# BonkSwitch.net
KiCad netlist of a schematic drawn in EAGLE
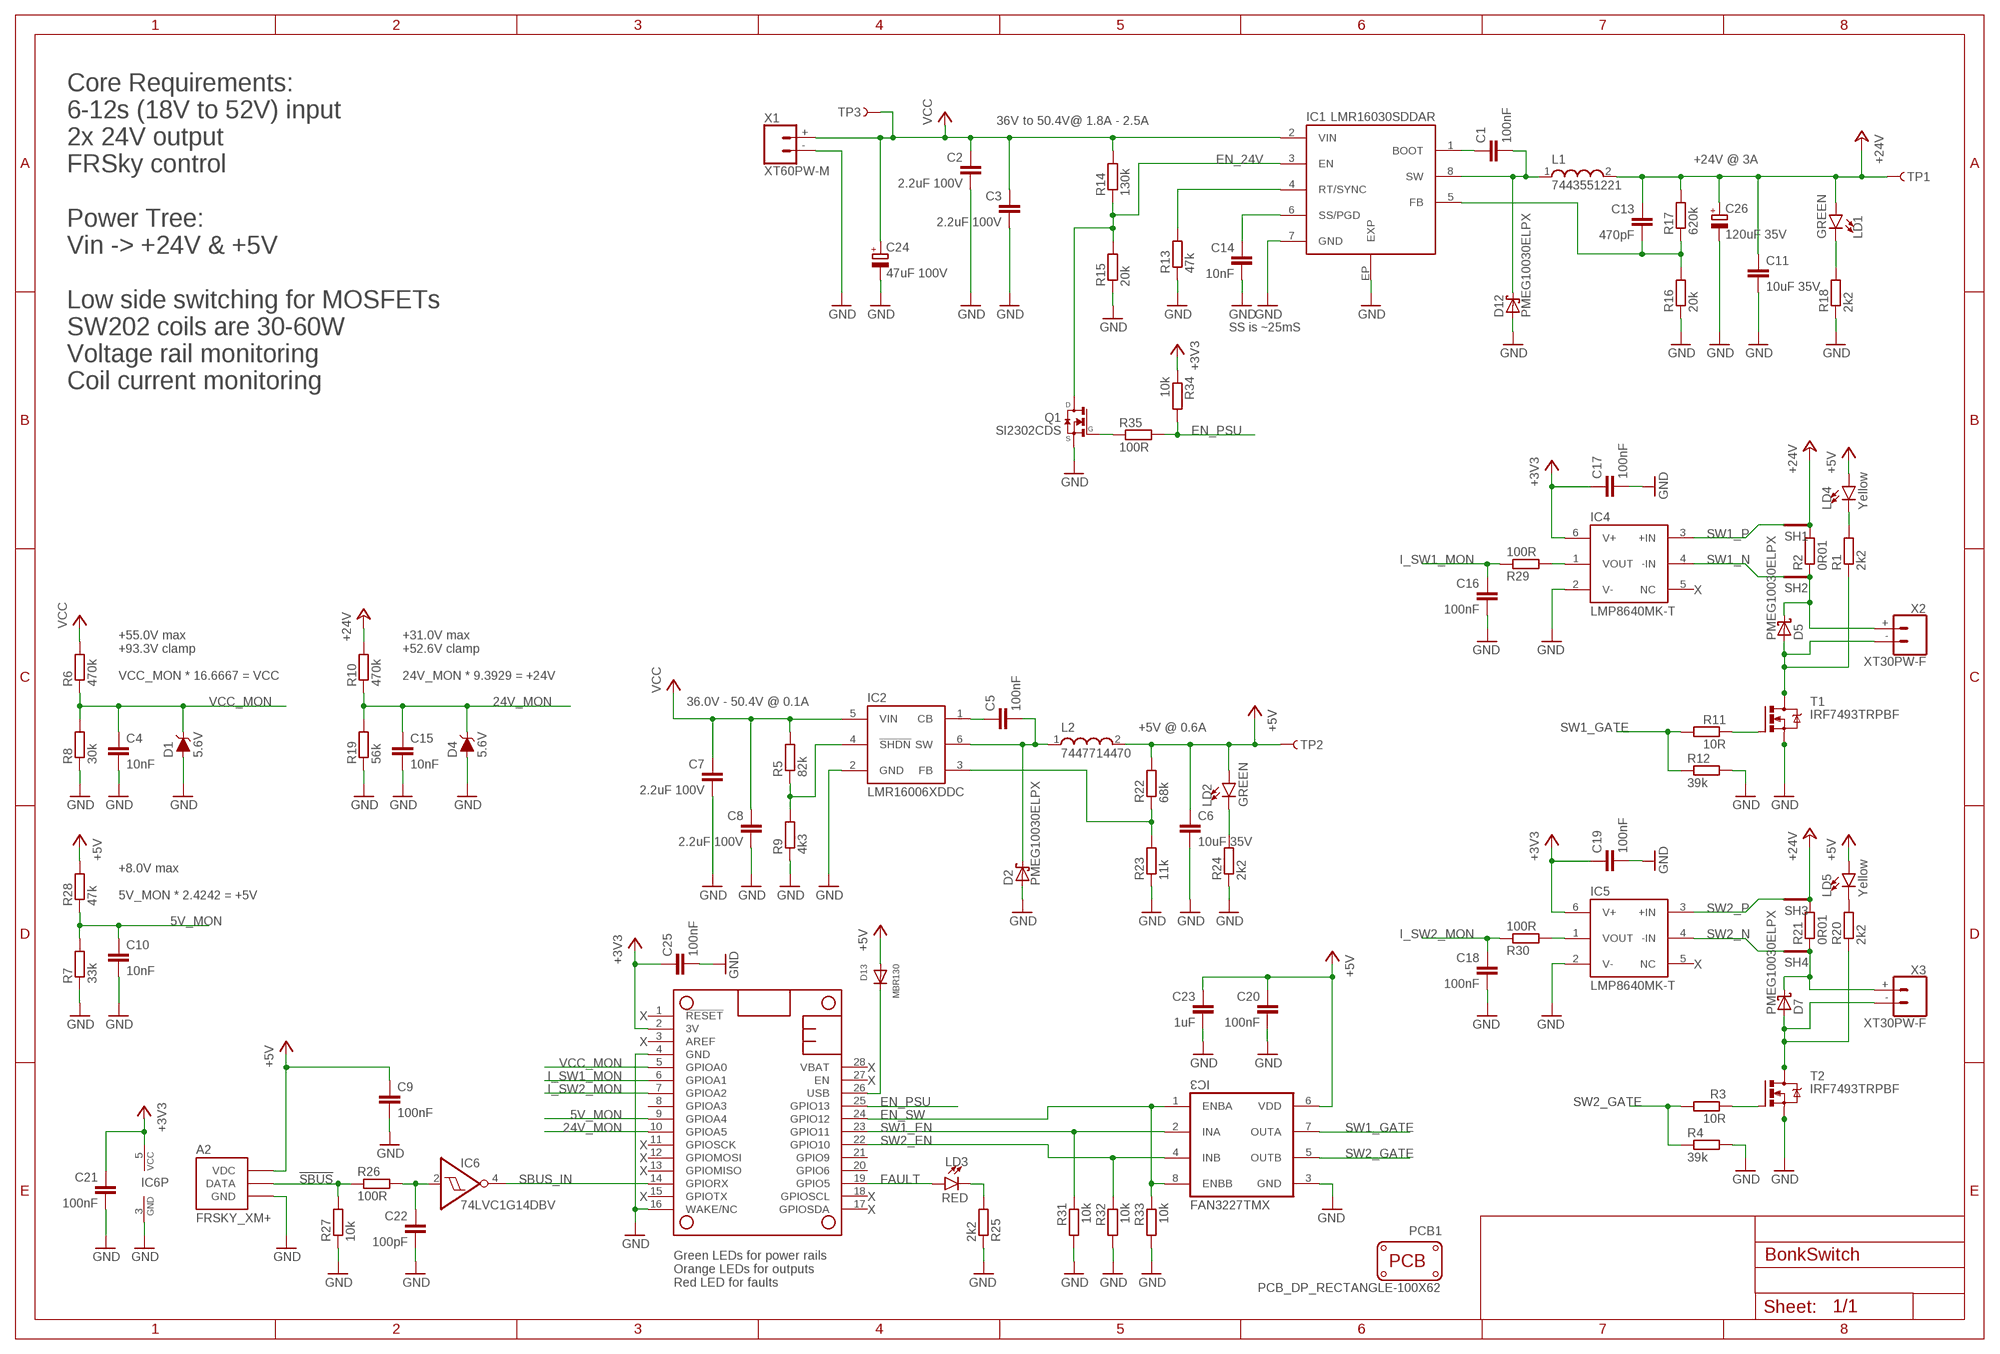
[diagram p0: schematic, sheet 1]

(export (version "E")
  (design (tool "Eeschema 10.0.6"))
  (components
    (comp (ref "A1")
      (value "FEATHERWING_NODIM")
      (footprint "eagle-import:FEATHERWING_DIM")
      (libsource (lib "eagle-import") (part "FEATHERWING_NODIM"))
    )
    (comp (ref "A2")
      (value "FRSKY_XM+")
      (footprint "eagle-import:FRSKY_XM+")
      (libsource (lib "eagle-import") (part "FRSKY_XM+"))
    )
    (comp (ref "C1")
      (value "100nF")
      (footprint "eagle-import:C0603")
      (libsource (lib "eagle-import") (part "C-EUC0603"))
    )
    (comp (ref "C2")
      (value "2.2uF 100V")
      (footprint "eagle-import:C1210")
      (fields (field (name "MF") "TDK") (field (name "MPN") "C3225X7R2A225K230AB"))
      (libsource (lib "eagle-import") (part "C-EUC1210"))
    )
    (comp (ref "C3")
      (value "2.2uF 100V")
      (footprint "eagle-import:C1210")
      (fields (field (name "MF") "TDK") (field (name "MPN") "C3225X7R2A225K230AB"))
      (libsource (lib "eagle-import") (part "C-EUC1210"))
    )
    (comp (ref "C4")
      (value "10nF")
      (footprint "eagle-import:C0603")
      (libsource (lib "eagle-import") (part "C-EUC0603"))
    )
    (comp (ref "C5")
      (value "100nF")
      (footprint "eagle-import:C0603")
      (libsource (lib "eagle-import") (part "C-EUC0603"))
    )
    (comp (ref "C6")
      (value "10uF 35V")
      (footprint "eagle-import:C1210")
      (fields (field (name "MF") "TAIYO YUDEN") (field (name "MPN") "GMK325AB7106MM-T"))
      (libsource (lib "eagle-import") (part "C-EUC1210"))
    )
    (comp (ref "C7")
      (value "2.2uF 100V")
      (footprint "eagle-import:C1210")
      (fields (field (name "MF") "TDK") (field (name "MPN") "C3225X7R2A225K230AB"))
      (libsource (lib "eagle-import") (part "C-EUC1210"))
    )
    (comp (ref "C8")
      (value "2.2uF 100V")
      (footprint "eagle-import:C1210")
      (fields (field (name "MF") "TDK") (field (name "MPN") "C3225X7R2A225K230AB"))
      (libsource (lib "eagle-import") (part "C-EUC1210"))
    )
    (comp (ref "C9")
      (value "100nF")
      (footprint "eagle-import:C0603")
      (libsource (lib "eagle-import") (part "C-EUC0603"))
    )
    (comp (ref "C10")
      (value "10nF")
      (footprint "eagle-import:C0603")
      (libsource (lib "eagle-import") (part "C-EUC0603"))
    )
    (comp (ref "C11")
      (value "10uF 35V")
      (footprint "eagle-import:C1210")
      (fields (field (name "MF") "TAIYO YUDEN") (field (name "MPN") "GMK325AB7106MM-T"))
      (libsource (lib "eagle-import") (part "C-EUC1210"))
    )
    (comp (ref "C13")
      (value "470pF")
      (footprint "eagle-import:C0603")
      (libsource (lib "eagle-import") (part "C-EUC0603"))
    )
    (comp (ref "C14")
      (value "10nF")
      (footprint "eagle-import:C0603")
      (libsource (lib "eagle-import") (part "C-EUC0603"))
    )
    (comp (ref "C15")
      (value "10nF")
      (footprint "eagle-import:C0603")
      (libsource (lib "eagle-import") (part "C-EUC0603"))
    )
    (comp (ref "C16")
      (value "100nF")
      (footprint "eagle-import:C0603")
      (libsource (lib "eagle-import") (part "C-EUC0603"))
    )
    (comp (ref "C17")
      (value "100nF")
      (footprint "eagle-import:C0603")
      (libsource (lib "eagle-import") (part "C-EUC0603"))
    )
    (comp (ref "C18")
      (value "100nF")
      (footprint "eagle-import:C0603")
      (libsource (lib "eagle-import") (part "C-EUC0603"))
    )
    (comp (ref "C19")
      (value "100nF")
      (footprint "eagle-import:C0603")
      (libsource (lib "eagle-import") (part "C-EUC0603"))
    )
    (comp (ref "C20")
      (value "100nF")
      (footprint "eagle-import:C0603")
      (libsource (lib "eagle-import") (part "C-EUC0603"))
    )
    (comp (ref "C21")
      (value "100nF")
      (footprint "eagle-import:C0603")
      (libsource (lib "eagle-import") (part "C-EUC0603"))
    )
    (comp (ref "C22")
      (value "100pF")
      (footprint "eagle-import:C0603")
      (libsource (lib "eagle-import") (part "C-EUC0603"))
    )
    (comp (ref "C23")
      (value "1uF")
      (footprint "eagle-import:C0805")
      (libsource (lib "eagle-import") (part "C-EUC0805"))
    )
    (comp (ref "C24")
      (value "47uF 100V")
      (footprint "eagle-import:UD-10X10_NICHICON")
      (fields (field (name "MF") "PANASONIC") (field (name "MPN") "EEEHA2A470UP"))
      (libsource (lib "eagle-import") (part "CPOL-EUUD-10X10"))
    )
    (comp (ref "C25")
      (value "100nF")
      (footprint "eagle-import:C0603")
      (libsource (lib "eagle-import") (part "C-EUC0603"))
    )
    (comp (ref "C26")
      (value "120uF 35V")
      (footprint "eagle-import:PANASONIC_E")
      (fields (field (name "MF") "PANASONIC") (field (name "MPN") "35SVPF120M"))
      (libsource (lib "eagle-import") (part "CPOL-EUE"))
    )
    (comp (ref "D1")
      (value "5.6V")
      (footprint "eagle-import:SOD-323")
      (fields (field (name "MF") "ON SEMICONDUCTOR") (field (name "MPN") "MM3Z4V3ST1G"))
      (libsource (lib "eagle-import") (part "DIODE-ZENER-MMSZ5232BS"))
    )
    (comp (ref "D2")
      (value "PMEG10030ELPX")
      (footprint "eagle-import:SOD128")
      (fields (field (name "MF") "NEXPERIA"))
      (libsource (lib "eagle-import") (part "SCHOTTKY-DIODESOD128"))
    )
    (comp (ref "D4")
      (value "5.6V")
      (footprint "eagle-import:SOD-323")
      (fields (field (name "MF") "ON SEMICONDUCTOR") (field (name "MPN") "MM3Z4V3ST1G"))
      (libsource (lib "eagle-import") (part "DIODE-ZENER-MMSZ5232BS"))
    )
    (comp (ref "D5")
      (value "PMEG10030ELPX")
      (footprint "eagle-import:SOD128")
      (fields (field (name "MF") "NEXPERIA"))
      (libsource (lib "eagle-import") (part "SCHOTTKY-DIODESOD128"))
    )
    (comp (ref "D7")
      (value "PMEG10030ELPX")
      (footprint "eagle-import:SOD128")
      (fields (field (name "MF") "NEXPERIA"))
      (libsource (lib "eagle-import") (part "SCHOTTKY-DIODESOD128"))
    )
    (comp (ref "D12")
      (value "PMEG10030ELPX")
      (footprint "eagle-import:SOD128")
      (fields (field (name "MF") "NEXPERIA"))
      (libsource (lib "eagle-import") (part "SCHOTTKY-DIODESOD128"))
    )
    (comp (ref "D13")
      (value "MBR130")
      (footprint "eagle-import:SOD-123")
      (fields (field (name "MF") "ON SEMICONDUCTOR") (field (name "MPN") "MBR130LSFT1G"))
      (libsource (lib "eagle-import") (part "DIODESOD-123"))
    )
    (comp (ref "IC1")
      (value "LMR16030SDDAR")
      (footprint "eagle-import:HSOIC8")
      (fields (field (name "MF") "TEXAS INSTRUMENTS") (field (name "MPN") "LMR16030SDDA ."))
      (libsource (lib "eagle-import") (part "LMR16030"))
    )
    (comp (ref "IC2")
      (value "LMR16006XDDC")
      (footprint "eagle-import:SOT23-6")
      (fields (field (name "MF") "TEXAS INSTRUMENTS") (field (name "MPN") "LMR16006XDDCR"))
      (libsource (lib "eagle-import") (part "LMR16006"))
    )
    (comp (ref "IC3")
      (value "FAN3227TMX")
      (footprint "eagle-import:SOIC127P600X175-8N")
      (fields
        (field (name "MPN") "UCC27424D")
        (field (name "MF") "ON SEMICONDUCTOR")
        (field (name "MPN_1") "FAN3227TMX")
        (field (name "OC_FARNELL") "2563218")
      )
      (libsource (lib "eagle-import") (part "UCC27424D"))
    )
    (comp (ref "IC4")
      (value "LMP8640MK-T")
      (footprint "eagle-import:SOT23-6")
      (fields (field (name "MF") "TEXAS INSTRUMENTS") (field (name "MPN") "LMP8640MK-T/NOPB"))
      (libsource (lib "eagle-import") (part "LMP8640"))
    )
    (comp (ref "IC5")
      (value "LMP8640MK-T")
      (footprint "eagle-import:SOT23-6")
      (fields (field (name "MF") "TEXAS INSTRUMENTS") (field (name "MPN") "LMP8640MK-T/NOPB"))
      (libsource (lib "eagle-import") (part "LMP8640"))
    )
    (comp (ref "IC6")
      (value "74LVC1G14DBV")
      (footprint "eagle-import:SOT23-5")
      (fields
        (field (name "MF") "NEXPERIA")
        (field (name "MPN") "74LVC1G14GW,125")
        (field (name "OC_FARNELL") "1631687")
      )
      (libsource (lib "eagle-import") (part "741G14DBVAHC"))
    )
    (comp (ref "L1")
      (value "7443551221")
      (footprint "eagle-import:WE-HCI_1350_1365")
      (fields (field (name "MF") "WURTH ELEKTRONIK"))
      (libsource (lib "eagle-import") (part "WE-HCI_1350/1365"))
    )
    (comp (ref "L2")
      (value "7447714470")
      (footprint "eagle-import:WE-PD_1030_1050")
      (fields (field (name "MF") "WURTH ELEKTRONIK"))
      (libsource (lib "eagle-import") (part "WE-PD_1030/1050"))
    )
    (comp (ref "LD1")
      (value "GREEN")
      (footprint "eagle-import:LED-0603")
      (libsource (lib "eagle-import") (part "LED-GREEN0603"))
    )
    (comp (ref "LD2")
      (value "GREEN")
      (footprint "eagle-import:LED-0603")
      (libsource (lib "eagle-import") (part "LED-GREEN0603"))
    )
    (comp (ref "LD3")
      (value "RED")
      (footprint "eagle-import:LED-0603")
      (libsource (lib "eagle-import") (part "LED-RED0603"))
    )
    (comp (ref "LD4")
      (value "Yellow")
      (footprint "eagle-import:LED-0603")
      (libsource (lib "eagle-import") (part "LED-YELLOW0603"))
    )
    (comp (ref "LD5")
      (value "Yellow")
      (footprint "eagle-import:LED-0603")
      (libsource (lib "eagle-import") (part "LED-YELLOW0603"))
    )
    (comp (ref "PCB1")
      (value "PCB_DP_RECTANGLE-100X62")
      (footprint "eagle-import:DP10062_V1")
      (libsource (lib "eagle-import") (part "PCB_DP_RECTANGLE-100X62"))
    )
    (comp (ref "Q1")
      (value "SI2302CDS")
      (footprint "eagle-import:SOT23")
      (fields (field (name "MF") "VISHAY") (field (name "MPN") "SI2302CDS-T1-GE3"))
      (libsource (lib "eagle-import") (part "SI2302"))
    )
    (comp (ref "R1")
      (value "2k2")
      (footprint "eagle-import:R0603")
      (libsource (lib "eagle-import") (part "R-EU_R0603"))
    )
    (comp (ref "R2")
      (value "0R01")
      (footprint "eagle-import:R2512")
      (fields (field (name "MF") "BOURNS") (field (name "MPN") "CRA2512-FZ-R010ELF"))
      (libsource (lib "eagle-import") (part "R-EU_R2512"))
    )
    (comp (ref "R3")
      (value "10R")
      (footprint "eagle-import:R0805")
      (libsource (lib "eagle-import") (part "R-EU_R0805"))
    )
    (comp (ref "R4")
      (value "39k")
      (footprint "eagle-import:R0805")
      (libsource (lib "eagle-import") (part "R-EU_R0805"))
    )
    (comp (ref "R5")
      (value "82k")
      (footprint "eagle-import:R0603")
      (libsource (lib "eagle-import") (part "R-EU_R0603"))
    )
    (comp (ref "R6")
      (value "470k")
      (footprint "eagle-import:R0603")
      (libsource (lib "eagle-import") (part "R-EU_R0603"))
    )
    (comp (ref "R7")
      (value "33k")
      (footprint "eagle-import:R0603")
      (libsource (lib "eagle-import") (part "R-EU_R0603"))
    )
    (comp (ref "R8")
      (value "30k")
      (footprint "eagle-import:R0603")
      (libsource (lib "eagle-import") (part "R-EU_R0603"))
    )
    (comp (ref "R9")
      (value "4k3")
      (footprint "eagle-import:R0603")
      (libsource (lib "eagle-import") (part "R-EU_R0603"))
    )
    (comp (ref "R10")
      (value "470k")
      (footprint "eagle-import:R0603")
      (libsource (lib "eagle-import") (part "R-EU_R0603"))
    )
    (comp (ref "R11")
      (value "10R")
      (footprint "eagle-import:R0805")
      (libsource (lib "eagle-import") (part "R-EU_R0805"))
    )
    (comp (ref "R12")
      (value "39k")
      (footprint "eagle-import:R0805")
      (libsource (lib "eagle-import") (part "R-EU_R0805"))
    )
    (comp (ref "R13")
      (value "47k")
      (footprint "eagle-import:R0603")
      (libsource (lib "eagle-import") (part "R-EU_R0603"))
    )
    (comp (ref "R14")
      (value "130k")
      (footprint "eagle-import:R0603")
      (libsource (lib "eagle-import") (part "R-EU_R0603"))
    )
    (comp (ref "R15")
      (value "20k")
      (footprint "eagle-import:R0603")
      (libsource (lib "eagle-import") (part "R-EU_R0603"))
    )
    (comp (ref "R16")
      (value "20k")
      (footprint "eagle-import:R0603")
      (libsource (lib "eagle-import") (part "R-EU_R0603"))
    )
    (comp (ref "R17")
      (value "620k")
      (footprint "eagle-import:R0603")
      (libsource (lib "eagle-import") (part "R-EU_R0603"))
    )
    (comp (ref "R18")
      (value "2k2")
      (footprint "eagle-import:R0805")
      (libsource (lib "eagle-import") (part "R-EU_R0805"))
    )
    (comp (ref "R19")
      (value "56k")
      (footprint "eagle-import:R0603")
      (libsource (lib "eagle-import") (part "R-EU_R0603"))
    )
    (comp (ref "R20")
      (value "2k2")
      (footprint "eagle-import:R0603")
      (libsource (lib "eagle-import") (part "R-EU_R0603"))
    )
    (comp (ref "R21")
      (value "0R01")
      (footprint "eagle-import:R2512")
      (fields (field (name "MF") "BOURNS") (field (name "MPN") "CRA2512-FZ-R010ELF"))
      (libsource (lib "eagle-import") (part "R-EU_R2512"))
    )
    (comp (ref "R22")
      (value "68k")
      (footprint "eagle-import:R0603")
      (libsource (lib "eagle-import") (part "R-EU_R0603"))
    )
    (comp (ref "R23")
      (value "11k")
      (footprint "eagle-import:R0603")
      (libsource (lib "eagle-import") (part "R-EU_R0603"))
    )
    (comp (ref "R24")
      (value "2k2")
      (footprint "eagle-import:R0603")
      (libsource (lib "eagle-import") (part "R-EU_R0603"))
    )
    (comp (ref "R25")
      (value "2k2")
      (footprint "eagle-import:R0603")
      (libsource (lib "eagle-import") (part "R-EU_R0603"))
    )
    (comp (ref "R26")
      (value "100R")
      (footprint "eagle-import:R0603")
      (libsource (lib "eagle-import") (part "R-EU_R0603"))
    )
    (comp (ref "R27")
      (value "10k")
      (footprint "eagle-import:R0603")
      (libsource (lib "eagle-import") (part "R-EU_R0603"))
    )
    (comp (ref "R28")
      (value "47k")
      (footprint "eagle-import:R0603")
      (libsource (lib "eagle-import") (part "R-EU_R0603"))
    )
    (comp (ref "R29")
      (value "100R")
      (footprint "eagle-import:R0603")
      (libsource (lib "eagle-import") (part "R-EU_R0603"))
    )
    (comp (ref "R30")
      (value "100R")
      (footprint "eagle-import:R0603")
      (libsource (lib "eagle-import") (part "R-EU_R0603"))
    )
    (comp (ref "R31")
      (value "10k")
      (footprint "eagle-import:R0603")
      (libsource (lib "eagle-import") (part "R-EU_R0603"))
    )
    (comp (ref "R32")
      (value "10k")
      (footprint "eagle-import:R0603")
      (libsource (lib "eagle-import") (part "R-EU_R0603"))
    )
    (comp (ref "R33")
      (value "10k")
      (footprint "eagle-import:R0603")
      (libsource (lib "eagle-import") (part "R-EU_R0603"))
    )
    (comp (ref "R34")
      (value "10k")
      (footprint "eagle-import:R0603")
      (libsource (lib "eagle-import") (part "R-EU_R0603"))
    )
    (comp (ref "R35")
      (value "100R")
      (footprint "eagle-import:R0603")
      (libsource (lib "eagle-import") (part "R-EU_R0603"))
    )
    (comp (ref "SH1")
      (value "SHORTT1")
      (footprint "eagle-import:SHORT_TOP-01")
      (libsource (lib "eagle-import") (part "SHORTT1"))
    )
    (comp (ref "SH2")
      (value "SHORTT1")
      (footprint "eagle-import:SHORT_TOP-01")
      (libsource (lib "eagle-import") (part "SHORTT1"))
    )
    (comp (ref "SH3")
      (value "SHORTT1")
      (footprint "eagle-import:SHORT_TOP-01")
      (libsource (lib "eagle-import") (part "SHORTT1"))
    )
    (comp (ref "SH4")
      (value "SHORTT1")
      (footprint "eagle-import:SHORT_TOP-01")
      (libsource (lib "eagle-import") (part "SHORTT1"))
    )
    (comp (ref "T1")
      (value "IRF7493TRPBF")
      (footprint "eagle-import:SO-08")
      (fields (field (name "MF") "INFINEON"))
      (libsource (lib "eagle-import") (part "N-MOSFET-SO8S"))
    )
    (comp (ref "T2")
      (value "IRF7493TRPBF")
      (footprint "eagle-import:SO-08")
      (fields (field (name "MF") "INFINEON"))
      (libsource (lib "eagle-import") (part "N-MOSFET-SO8S"))
    )
    (comp (ref "TP1")
      (value "TESTPOINT_1.5X1.5")
      (footprint "eagle-import:TESTPAD_1.5X1.5")
      (libsource (lib "eagle-import") (part "TESTPOINT_1.5X1.5"))
    )
    (comp (ref "TP2")
      (value "TESTPOINT_1.5X1.5")
      (footprint "eagle-import:TESTPAD_1.5X1.5")
      (libsource (lib "eagle-import") (part "TESTPOINT_1.5X1.5"))
    )
    (comp (ref "TP3")
      (value "TESTPOINT_1.5X1.5")
      (footprint "eagle-import:TESTPAD_1.5X1.5")
      (libsource (lib "eagle-import") (part "TESTPOINT_1.5X1.5"))
    )
    (comp (ref "X1")
      (value "XT60PW-M")
      (footprint "eagle-import:XT60PW-M")
      (libsource (lib "eagle-import") (part "XT60PW-M"))
    )
    (comp (ref "X2")
      (value "XT30PW-F")
      (footprint "eagle-import:XT30PW-F")
      (libsource (lib "eagle-import") (part "XT30PW-F"))
    )
    (comp (ref "X3")
      (value "XT30PW-F")
      (footprint "eagle-import:XT30PW-F")
      (libsource (lib "eagle-import") (part "XT30PW-F"))
    )
  )
  (nets
    (net (code "1") (name "+3V3") (class "Default")
      (node (ref "A1") (pin "2") (pinfunction "3V_2") (pintype "power_in"))
      (node (ref "C17") (pin "1") (pinfunction "1_1") (pintype "passive"))
      (node (ref "C19") (pin "1") (pinfunction "1_1") (pintype "passive"))
      (node (ref "C21") (pin "1") (pinfunction "1_1") (pintype "passive"))
      (node (ref "C25") (pin "1") (pinfunction "1_1") (pintype "passive"))
      (node (ref "IC4") (pin "6") (pinfunction "V+_6") (pintype "bidirectional"))
      (node (ref "IC5") (pin "6") (pinfunction "V+_6") (pintype "bidirectional"))
      (node (ref "IC6") (pin "5") (pinfunction "VCC_5") (pintype "power_in"))
      (node (ref "R34") (pin "1") (pinfunction "1_1") (pintype "passive"))
    )
    (net (code "2") (name "+5V") (class "Default")
      (node (ref "A2") (pin "2") (pinfunction "VDC_2") (pintype "bidirectional"))
      (node (ref "C20") (pin "1") (pinfunction "1_1") (pintype "passive"))
      (node (ref "C23") (pin "1") (pinfunction "1_1") (pintype "passive"))
      (node (ref "C6") (pin "1") (pinfunction "1_1") (pintype "passive"))
      (node (ref "C9") (pin "1") (pinfunction "1_1") (pintype "passive"))
      (node (ref "D13") (pin "A") (pinfunction "A_A") (pintype "passive"))
      (node (ref "IC3") (pin "6") (pinfunction "VDD_6") (pintype "power_in"))
      (node (ref "L2") (pin "2") (pinfunction "2_2") (pintype "passive"))
      (node (ref "LD2") (pin "A") (pinfunction "A_A") (pintype "passive"))
      (node (ref "LD4") (pin "A") (pinfunction "A_A") (pintype "passive"))
      (node (ref "LD5") (pin "A") (pinfunction "A_A") (pintype "passive"))
      (node (ref "R22") (pin "2") (pinfunction "2_2") (pintype "passive"))
      (node (ref "R28") (pin "2") (pinfunction "2_2") (pintype "passive"))
      (node (ref "TP2") (pin "1") (pinfunction "1_1") (pintype "bidirectional"))
    )
    (net (code "3") (name "+24V") (class "Default")
      (node (ref "C11") (pin "1") (pinfunction "1_1") (pintype "passive"))
      (node (ref "C13") (pin "1") (pinfunction "1_1") (pintype "passive"))
      (node (ref "C26") (pin "+") (pinfunction "+_+") (pintype "passive"))
      (node (ref "L1") (pin "2") (pinfunction "2_2") (pintype "passive"))
      (node (ref "LD1") (pin "A") (pinfunction "A_A") (pintype "passive"))
      (node (ref "R10") (pin "2") (pinfunction "2_2") (pintype "passive"))
      (node (ref "R17") (pin "2") (pinfunction "2_2") (pintype "passive"))
      (node (ref "R2") (pin "2") (pinfunction "2_2") (pintype "passive"))
      (node (ref "R21") (pin "2") (pinfunction "2_2") (pintype "passive"))
      (node (ref "SH1") (pin "1") (pinfunction "P$1_1") (pintype "bidirectional"))
      (node (ref "SH3") (pin "1") (pinfunction "P$1_1") (pintype "bidirectional"))
      (node (ref "TP1") (pin "1") (pinfunction "1_1") (pintype "bidirectional"))
    )
    (net (code "4") (name "/5V_MON") (class "Default")
      (node (ref "A1") (pin "9") (pinfunction "GPIOA4_9") (pintype "bidirectional"))
      (node (ref "C10") (pin "1") (pinfunction "1_1") (pintype "passive"))
      (node (ref "R28") (pin "1") (pinfunction "1_1") (pintype "passive"))
      (node (ref "R7") (pin "2") (pinfunction "2_2") (pintype "passive"))
    )
    (net (code "5") (name "/24V_MON") (class "Default")
      (node (ref "A1") (pin "10") (pinfunction "GPIOA5_10") (pintype "bidirectional"))
      (node (ref "C15") (pin "1") (pinfunction "1_1") (pintype "passive"))
      (node (ref "D4") (pin "C") (pinfunction "C_C") (pintype "passive"))
      (node (ref "R10") (pin "1") (pinfunction "1_1") (pintype "passive"))
      (node (ref "R19") (pin "2") (pinfunction "2_2") (pintype "passive"))
    )
    (net (code "6") (name "/EN_24V") (class "Default")
      (node (ref "IC1") (pin "3") (pinfunction "EN_3") (pintype "bidirectional"))
      (node (ref "Q1") (pin "3") (pinfunction "D_3") (pintype "passive"))
      (node (ref "R14") (pin "1") (pinfunction "1_1") (pintype "passive"))
      (node (ref "R15") (pin "2") (pinfunction "2_2") (pintype "passive"))
    )
    (net (code "7") (name "/EN_PSU") (class "Default")
      (node (ref "A1") (pin "25") (pinfunction "GPIO13_25") (pintype "bidirectional"))
      (node (ref "R34") (pin "2") (pinfunction "2_2") (pintype "passive"))
      (node (ref "R35") (pin "2") (pinfunction "2_2") (pintype "passive"))
    )
    (net (code "8") (name "/EN_SW") (class "Default")
      (node (ref "A1") (pin "24") (pinfunction "GPIO12_24") (pintype "bidirectional"))
      (node (ref "IC3") (pin "1") (pinfunction "ENBA_1") (pintype "input"))
      (node (ref "IC3") (pin "8") (pinfunction "ENBB_8") (pintype "input"))
      (node (ref "R33") (pin "1") (pinfunction "1_1") (pintype "passive"))
    )
    (net (code "9") (name "/FAULT") (class "Default")
      (node (ref "A1") (pin "19") (pinfunction "GPIO5_19") (pintype "bidirectional"))
      (node (ref "LD3") (pin "A") (pinfunction "A_A") (pintype "passive"))
    )
    (net (code "10") (name "/I_SW1_MON") (class "Default")
      (node (ref "A1") (pin "6") (pinfunction "GPIOA1_6") (pintype "bidirectional"))
      (node (ref "C16") (pin "1") (pinfunction "1_1") (pintype "passive"))
      (node (ref "R29") (pin "1") (pinfunction "1_1") (pintype "passive"))
    )
    (net (code "11") (name "/I_SW2_MON") (class "Default")
      (node (ref "A1") (pin "7") (pinfunction "GPIOA2_7") (pintype "bidirectional"))
      (node (ref "C18") (pin "1") (pinfunction "1_1") (pintype "passive"))
      (node (ref "R30") (pin "1") (pinfunction "1_1") (pintype "passive"))
    )
    (net (code "12") (name "/SBUS_IN") (class "Default")
      (node (ref "A1") (pin "14") (pinfunction "GPIORX_14") (pintype "bidirectional"))
      (node (ref "IC6") (pin "4") (pinfunction "O_4") (pintype "output"))
    )
    (net (code "13") (name "/SW1_EN") (class "Default")
      (node (ref "A1") (pin "23") (pinfunction "GPIO11_23") (pintype "bidirectional"))
      (node (ref "IC3") (pin "2") (pinfunction "INA_2") (pintype "input"))
      (node (ref "R31") (pin "1") (pinfunction "1_1") (pintype "passive"))
    )
    (net (code "14") (name "/SW1_GATE") (class "Default")
      (node (ref "IC3") (pin "7") (pinfunction "OUTA_7") (pintype "output"))
      (node (ref "R11") (pin "2") (pinfunction "2_2") (pintype "passive"))
      (node (ref "R12") (pin "1") (pinfunction "1_1") (pintype "passive"))
    )
    (net (code "15") (name "/SW1_N") (class "Default")
      (node (ref "IC4") (pin "4") (pinfunction "-IN_4") (pintype "bidirectional"))
      (node (ref "SH2") (pin "2") (pinfunction "P$2_2") (pintype "bidirectional"))
    )
    (net (code "16") (name "/SW1_P") (class "Default")
      (node (ref "IC4") (pin "3") (pinfunction "+IN_3") (pintype "bidirectional"))
      (node (ref "SH1") (pin "2") (pinfunction "P$2_2") (pintype "bidirectional"))
    )
    (net (code "17") (name "/SW2_EN") (class "Default")
      (node (ref "A1") (pin "22") (pinfunction "GPIO10_22") (pintype "bidirectional"))
      (node (ref "IC3") (pin "4") (pinfunction "INB_4") (pintype "input"))
      (node (ref "R32") (pin "1") (pinfunction "1_1") (pintype "passive"))
    )
    (net (code "18") (name "/SW2_GATE") (class "Default")
      (node (ref "IC3") (pin "5") (pinfunction "OUTB_5") (pintype "output"))
      (node (ref "R3") (pin "2") (pinfunction "2_2") (pintype "passive"))
      (node (ref "R4") (pin "1") (pinfunction "1_1") (pintype "passive"))
    )
    (net (code "19") (name "/SW2_N") (class "Default")
      (node (ref "IC5") (pin "4") (pinfunction "-IN_4") (pintype "bidirectional"))
      (node (ref "SH4") (pin "2") (pinfunction "P$2_2") (pintype "bidirectional"))
    )
    (net (code "20") (name "/SW2_P") (class "Default")
      (node (ref "IC5") (pin "3") (pinfunction "+IN_3") (pintype "bidirectional"))
      (node (ref "SH3") (pin "2") (pinfunction "P$2_2") (pintype "bidirectional"))
    )
    (net (code "21") (name "/VBAT") (class "Default")
      (node (ref "A1") (pin "28") (pinfunction "VBAT_28") (pintype "power_in"))
    )
    (net (code "22") (name "/VCC_MON") (class "Default")
      (node (ref "A1") (pin "5") (pinfunction "GPIOA0_5") (pintype "bidirectional"))
      (node (ref "C4") (pin "1") (pinfunction "1_1") (pintype "passive"))
      (node (ref "D1") (pin "C") (pinfunction "C_C") (pintype "passive"))
      (node (ref "R6") (pin "1") (pinfunction "1_1") (pintype "passive"))
      (node (ref "R8") (pin "2") (pinfunction "2_2") (pintype "passive"))
    )
    (net (code "23") (name "/~{SBUS}") (class "Default")
      (node (ref "A2") (pin "3") (pinfunction "DATA_3") (pintype "bidirectional"))
      (node (ref "R26") (pin "1") (pinfunction "1_1") (pintype "passive"))
      (node (ref "R27") (pin "2") (pinfunction "2_2") (pintype "passive"))
    )
    (net (code "24") (name "GND") (class "Default")
      (node (ref "A1") (pin "16") (pinfunction "WAKE/NC_16") (pintype "passive"))
      (node (ref "A1") (pin "4") (pinfunction "GND_4") (pintype "power_in"))
      (node (ref "A2") (pin "1") (pinfunction "GND_1") (pintype "bidirectional"))
      (node (ref "C10") (pin "2") (pinfunction "2_2") (pintype "passive"))
      (node (ref "C11") (pin "2") (pinfunction "2_2") (pintype "passive"))
      (node (ref "C14") (pin "2") (pinfunction "2_2") (pintype "passive"))
      (node (ref "C15") (pin "2") (pinfunction "2_2") (pintype "passive"))
      (node (ref "C16") (pin "2") (pinfunction "2_2") (pintype "passive"))
      (node (ref "C17") (pin "2") (pinfunction "2_2") (pintype "passive"))
      (node (ref "C18") (pin "2") (pinfunction "2_2") (pintype "passive"))
      (node (ref "C19") (pin "2") (pinfunction "2_2") (pintype "passive"))
      (node (ref "C2") (pin "2") (pinfunction "2_2") (pintype "passive"))
      (node (ref "C20") (pin "2") (pinfunction "2_2") (pintype "passive"))
      (node (ref "C21") (pin "2") (pinfunction "2_2") (pintype "passive"))
      (node (ref "C22") (pin "2") (pinfunction "2_2") (pintype "passive"))
      (node (ref "C23") (pin "2") (pinfunction "2_2") (pintype "passive"))
      (node (ref "C24") (pin "-") (pinfunction "-_-") (pintype "passive"))
      (node (ref "C25") (pin "2") (pinfunction "2_2") (pintype "passive"))
      (node (ref "C26") (pin "-") (pinfunction "-_-") (pintype "passive"))
      (node (ref "C3") (pin "2") (pinfunction "2_2") (pintype "passive"))
      (node (ref "C4") (pin "2") (pinfunction "2_2") (pintype "passive"))
      (node (ref "C6") (pin "2") (pinfunction "2_2") (pintype "passive"))
      (node (ref "C7") (pin "2") (pinfunction "2_2") (pintype "passive"))
      (node (ref "C8") (pin "2") (pinfunction "2_2") (pintype "passive"))
      (node (ref "C9") (pin "2") (pinfunction "2_2") (pintype "passive"))
      (node (ref "D1") (pin "A") (pinfunction "A_A") (pintype "passive"))
      (node (ref "D12") (pin "A") (pinfunction "A_A") (pintype "passive"))
      (node (ref "D2") (pin "A") (pinfunction "A_A") (pintype "passive"))
      (node (ref "D4") (pin "A") (pinfunction "A_A") (pintype "passive"))
      (node (ref "IC1") (pin "7") (pinfunction "GND_7") (pintype "bidirectional"))
      (node (ref "IC1") (pin "EP") (pinfunction "EXP_EP") (pintype "bidirectional"))
      (node (ref "IC2") (pin "2") (pinfunction "GND_2") (pintype "bidirectional"))
      (node (ref "IC3") (pin "3") (pinfunction "GND_3") (pintype "passive"))
      (node (ref "IC4") (pin "2") (pinfunction "V-_2") (pintype "bidirectional"))
      (node (ref "IC5") (pin "2") (pinfunction "V-_2") (pintype "bidirectional"))
      (node (ref "IC6") (pin "3") (pinfunction "GND_3") (pintype "power_in"))
      (node (ref "Q1") (pin "2") (pinfunction "S_2") (pintype "passive"))
      (node (ref "R12") (pin "2") (pinfunction "2_2") (pintype "passive"))
      (node (ref "R13") (pin "1") (pinfunction "1_1") (pintype "passive"))
      (node (ref "R15") (pin "1") (pinfunction "1_1") (pintype "passive"))
      (node (ref "R16") (pin "1") (pinfunction "1_1") (pintype "passive"))
      (node (ref "R18") (pin "1") (pinfunction "1_1") (pintype "passive"))
      (node (ref "R19") (pin "1") (pinfunction "1_1") (pintype "passive"))
      (node (ref "R23") (pin "1") (pinfunction "1_1") (pintype "passive"))
      (node (ref "R24") (pin "1") (pinfunction "1_1") (pintype "passive"))
      (node (ref "R25") (pin "1") (pinfunction "1_1") (pintype "passive"))
      (node (ref "R27") (pin "1") (pinfunction "1_1") (pintype "passive"))
      (node (ref "R31") (pin "2") (pinfunction "2_2") (pintype "passive"))
      (node (ref "R32") (pin "2") (pinfunction "2_2") (pintype "passive"))
      (node (ref "R33") (pin "2") (pinfunction "2_2") (pintype "passive"))
      (node (ref "R4") (pin "2") (pinfunction "2_2") (pintype "passive"))
      (node (ref "R7") (pin "1") (pinfunction "1_1") (pintype "passive"))
      (node (ref "R8") (pin "1") (pinfunction "1_1") (pintype "passive"))
      (node (ref "R9") (pin "1") (pinfunction "1_1") (pintype "passive"))
      (node (ref "T1") (pin "1") (pinfunction "S_1") (pintype "passive"))
      (node (ref "T1") (pin "2") (pinfunction "S_2") (pintype "passive"))
      (node (ref "T1") (pin "3") (pinfunction "S_3") (pintype "passive"))
      (node (ref "T2") (pin "1") (pinfunction "S_1") (pintype "passive"))
      (node (ref "T2") (pin "2") (pinfunction "S_2") (pintype "passive"))
      (node (ref "T2") (pin "3") (pinfunction "S_3") (pintype "passive"))
      (node (ref "X1") (pin "-") (pinfunction "1_-") (pintype "passive"))
    )
    (net (code "25") (name "Net-(A1-USB)") (class "Default")
      (node (ref "A1") (pin "26") (pinfunction "USB_26") (pintype "power_in"))
      (node (ref "D13") (pin "C") (pinfunction "C_C") (pintype "passive"))
    )
    (net (code "26") (name "Net-(IC1-BOOT)") (class "Default")
      (node (ref "C1") (pin "1") (pinfunction "1_1") (pintype "passive"))
      (node (ref "IC1") (pin "1") (pinfunction "BOOT_1") (pintype "bidirectional"))
    )
    (net (code "27") (name "Net-(IC1-FB)") (class "Default")
      (node (ref "C13") (pin "2") (pinfunction "2_2") (pintype "passive"))
      (node (ref "IC1") (pin "5") (pinfunction "FB_5") (pintype "bidirectional"))
      (node (ref "R16") (pin "2") (pinfunction "2_2") (pintype "passive"))
      (node (ref "R17") (pin "1") (pinfunction "1_1") (pintype "passive"))
    )
    (net (code "28") (name "Net-(IC1-RT{slash}SYNC)") (class "Default")
      (node (ref "IC1") (pin "4") (pinfunction "RT/SYNC_4") (pintype "bidirectional"))
      (node (ref "R13") (pin "2") (pinfunction "2_2") (pintype "passive"))
    )
    (net (code "29") (name "Net-(IC1-SS{slash}PGD)") (class "Default")
      (node (ref "C14") (pin "1") (pinfunction "1_1") (pintype "passive"))
      (node (ref "IC1") (pin "6") (pinfunction "SS/PGD_6") (pintype "bidirectional"))
    )
    (net (code "30") (name "Net-(IC1-SW)") (class "Default")
      (node (ref "C1") (pin "2") (pinfunction "2_2") (pintype "passive"))
      (node (ref "D12") (pin "C") (pinfunction "C_C") (pintype "passive"))
      (node (ref "IC1") (pin "8") (pinfunction "SW_8") (pintype "bidirectional"))
      (node (ref "L1") (pin "1") (pinfunction "1_1") (pintype "passive"))
    )
    (net (code "31") (name "Net-(IC2-CB)") (class "Default")
      (node (ref "C5") (pin "1") (pinfunction "1_1") (pintype "passive"))
      (node (ref "IC2") (pin "1") (pinfunction "CB_1") (pintype "bidirectional"))
    )
    (net (code "32") (name "Net-(IC2-FB)") (class "Default")
      (node (ref "IC2") (pin "3") (pinfunction "FB_3") (pintype "bidirectional"))
      (node (ref "R22") (pin "1") (pinfunction "1_1") (pintype "passive"))
      (node (ref "R23") (pin "2") (pinfunction "2_2") (pintype "passive"))
    )
    (net (code "33") (name "Net-(IC2-SW)") (class "Default")
      (node (ref "C5") (pin "2") (pinfunction "2_2") (pintype "passive"))
      (node (ref "D2") (pin "C") (pinfunction "C_C") (pintype "passive"))
      (node (ref "IC2") (pin "6") (pinfunction "SW_6") (pintype "bidirectional"))
      (node (ref "L2") (pin "1") (pinfunction "1_1") (pintype "passive"))
    )
    (net (code "34") (name "Net-(IC2-~{SHDN})") (class "Default")
      (node (ref "IC2") (pin "4") (pinfunction "~{SHDN}_4") (pintype "bidirectional"))
      (node (ref "R5") (pin "1") (pinfunction "1_1") (pintype "passive"))
      (node (ref "R9") (pin "2") (pinfunction "2_2") (pintype "passive"))
    )
    (net (code "35") (name "Net-(IC4-VOUT)") (class "Default")
      (node (ref "IC4") (pin "1") (pinfunction "VOUT_1") (pintype "bidirectional"))
      (node (ref "R29") (pin "2") (pinfunction "2_2") (pintype "passive"))
    )
    (net (code "36") (name "Net-(IC5-VOUT)") (class "Default")
      (node (ref "IC5") (pin "1") (pinfunction "VOUT_1") (pintype "bidirectional"))
      (node (ref "R30") (pin "2") (pinfunction "2_2") (pintype "passive"))
    )
    (net (code "37") (name "Net-(IC6A-I)") (class "Default")
      (node (ref "C22") (pin "1") (pinfunction "1_1") (pintype "passive"))
      (node (ref "IC6") (pin "2") (pinfunction "I_2") (pintype "input"))
      (node (ref "R26") (pin "2") (pinfunction "2_2") (pintype "passive"))
    )
    (net (code "38") (name "Net-(LD1-PadC)") (class "Default")
      (node (ref "LD1") (pin "C") (pinfunction "C_C") (pintype "passive"))
      (node (ref "R18") (pin "2") (pinfunction "2_2") (pintype "passive"))
    )
    (net (code "39") (name "Net-(LD2-PadC)") (class "Default")
      (node (ref "LD2") (pin "C") (pinfunction "C_C") (pintype "passive"))
      (node (ref "R24") (pin "2") (pinfunction "2_2") (pintype "passive"))
    )
    (net (code "40") (name "Net-(LD3-PadC)") (class "Default")
      (node (ref "LD3") (pin "C") (pinfunction "C_C") (pintype "passive"))
      (node (ref "R25") (pin "2") (pinfunction "2_2") (pintype "passive"))
    )
    (net (code "41") (name "Net-(LD4-PadC)") (class "Default")
      (node (ref "LD4") (pin "C") (pinfunction "C_C") (pintype "passive"))
      (node (ref "R1") (pin "2") (pinfunction "2_2") (pintype "passive"))
    )
    (net (code "42") (name "Net-(LD5-PadC)") (class "Default")
      (node (ref "LD5") (pin "C") (pinfunction "C_C") (pintype "passive"))
      (node (ref "R20") (pin "2") (pinfunction "2_2") (pintype "passive"))
    )
    (net (code "43") (name "Net-(Q1-G)") (class "Default")
      (node (ref "Q1") (pin "1") (pinfunction "G_1") (pintype "passive"))
      (node (ref "R35") (pin "1") (pinfunction "1_1") (pintype "passive"))
    )
    (net (code "44") (name "Net-(SH2-P$1)") (class "Default")
      (node (ref "D5") (pin "C") (pinfunction "C_C") (pintype "passive"))
      (node (ref "R2") (pin "1") (pinfunction "1_1") (pintype "passive"))
      (node (ref "SH2") (pin "1") (pinfunction "P$1_1") (pintype "bidirectional"))
      (node (ref "X2") (pin "+") (pinfunction "2_+") (pintype "passive"))
    )
    (net (code "45") (name "Net-(SH4-P$1)") (class "Default")
      (node (ref "D7") (pin "C") (pinfunction "C_C") (pintype "passive"))
      (node (ref "R21") (pin "1") (pinfunction "1_1") (pintype "passive"))
      (node (ref "SH4") (pin "1") (pinfunction "P$1_1") (pintype "bidirectional"))
      (node (ref "X3") (pin "+") (pinfunction "2_+") (pintype "passive"))
    )
    (net (code "46") (name "Net-(T1-G)") (class "Default")
      (node (ref "R11") (pin "1") (pinfunction "1_1") (pintype "passive"))
      (node (ref "T1") (pin "4") (pinfunction "G_4") (pintype "passive"))
    )
    (net (code "47") (name "Net-(T2-G)") (class "Default")
      (node (ref "R3") (pin "1") (pinfunction "1_1") (pintype "passive"))
      (node (ref "T2") (pin "4") (pinfunction "G_4") (pintype "passive"))
    )
    (net (code "48") (name "Net-(X2-1)") (class "Default")
      (node (ref "D5") (pin "A") (pinfunction "A_A") (pintype "passive"))
      (node (ref "R1") (pin "1") (pinfunction "1_1") (pintype "passive"))
      (node (ref "T1") (pin "5") (pinfunction "D_5") (pintype "passive"))
      (node (ref "T1") (pin "6") (pinfunction "D_6") (pintype "passive"))
      (node (ref "T1") (pin "7") (pinfunction "D_7") (pintype "passive"))
      (node (ref "T1") (pin "8") (pinfunction "D_8") (pintype "passive"))
      (node (ref "X2") (pin "-") (pinfunction "1_-") (pintype "passive"))
    )
    (net (code "49") (name "Net-(X3-1)") (class "Default")
      (node (ref "D7") (pin "A") (pinfunction "A_A") (pintype "passive"))
      (node (ref "R20") (pin "1") (pinfunction "1_1") (pintype "passive"))
      (node (ref "T2") (pin "5") (pinfunction "D_5") (pintype "passive"))
      (node (ref "T2") (pin "6") (pinfunction "D_6") (pintype "passive"))
      (node (ref "T2") (pin "7") (pinfunction "D_7") (pintype "passive"))
      (node (ref "T2") (pin "8") (pinfunction "D_8") (pintype "passive"))
      (node (ref "X3") (pin "-") (pinfunction "1_-") (pintype "passive"))
    )
    (net (code "50") (name "VCC") (class "Default")
      (node (ref "C2") (pin "1") (pinfunction "1_1") (pintype "passive"))
      (node (ref "C24") (pin "+") (pinfunction "+_+") (pintype "passive"))
      (node (ref "C3") (pin "1") (pinfunction "1_1") (pintype "passive"))
      (node (ref "C7") (pin "1") (pinfunction "1_1") (pintype "passive"))
      (node (ref "C8") (pin "1") (pinfunction "1_1") (pintype "passive"))
      (node (ref "IC1") (pin "2") (pinfunction "VIN_2") (pintype "bidirectional"))
      (node (ref "IC2") (pin "5") (pinfunction "VIN_5") (pintype "bidirectional"))
      (node (ref "R14") (pin "2") (pinfunction "2_2") (pintype "passive"))
      (node (ref "R5") (pin "2") (pinfunction "2_2") (pintype "passive"))
      (node (ref "R6") (pin "2") (pinfunction "2_2") (pintype "passive"))
      (node (ref "TP3") (pin "1") (pinfunction "1_1") (pintype "bidirectional"))
      (node (ref "X1") (pin "+") (pinfunction "2_+") (pintype "passive"))
    )
    (net (code "51") (name "unconnected-(A1-AREF-Pad3)") (class "Default")
      (node (ref "A1") (pin "3") (pinfunction "AREF_3") (pintype "passive"))
    )
    (net (code "52") (name "unconnected-(A1-EN-Pad27)") (class "Default")
      (node (ref "A1") (pin "27") (pinfunction "EN_27") (pintype "passive"))
    )
    (net (code "53") (name "unconnected-(A1-GPIO6-Pad20)") (class "Default")
      (node (ref "A1") (pin "20") (pinfunction "GPIO6_20") (pintype "bidirectional"))
    )
    (net (code "54") (name "unconnected-(A1-GPIO9-Pad21)") (class "Default")
      (node (ref "A1") (pin "21") (pinfunction "GPIO9_21") (pintype "bidirectional"))
    )
    (net (code "55") (name "unconnected-(A1-GPIOA3-Pad8)") (class "Default")
      (node (ref "A1") (pin "8") (pinfunction "GPIOA3_8") (pintype "bidirectional"))
    )
    (net (code "56") (name "unconnected-(A1-GPIOMISO-Pad13)") (class "Default")
      (node (ref "A1") (pin "13") (pinfunction "GPIOMISO_13") (pintype "bidirectional"))
    )
    (net (code "57") (name "unconnected-(A1-GPIOMOSI-Pad12)") (class "Default")
      (node (ref "A1") (pin "12") (pinfunction "GPIOMOSI_12") (pintype "bidirectional"))
    )
    (net (code "58") (name "unconnected-(A1-GPIOSCK-Pad11)") (class "Default")
      (node (ref "A1") (pin "11") (pinfunction "GPIOSCK_11") (pintype "bidirectional"))
    )
    (net (code "59") (name "unconnected-(A1-GPIOSCL-Pad18)") (class "Default")
      (node (ref "A1") (pin "18") (pinfunction "GPIOSCL_18") (pintype "bidirectional"))
    )
    (net (code "60") (name "unconnected-(A1-GPIOSDA-Pad17)") (class "Default")
      (node (ref "A1") (pin "17") (pinfunction "GPIOSDA_17") (pintype "bidirectional"))
    )
    (net (code "61") (name "unconnected-(A1-GPIOTX-Pad15)") (class "Default")
      (node (ref "A1") (pin "15") (pinfunction "GPIOTX_15") (pintype "bidirectional"))
    )
    (net (code "62") (name "unconnected-(A1-~{RESET}-Pad1)") (class "Default")
      (node (ref "A1") (pin "1") (pinfunction "~{RESET}_1") (pintype "input"))
    )
    (net (code "63") (name "unconnected-(IC4-NC-Pad5)") (class "Default")
      (node (ref "IC4") (pin "5") (pinfunction "NC_5") (pintype "bidirectional"))
    )
    (net (code "64") (name "unconnected-(IC5-NC-Pad5)") (class "Default")
      (node (ref "IC5") (pin "5") (pinfunction "NC_5") (pintype "bidirectional"))
    )
  )
)
